# ComboBreaker.net
KiCad netlist of a schematic drawn in EAGLE
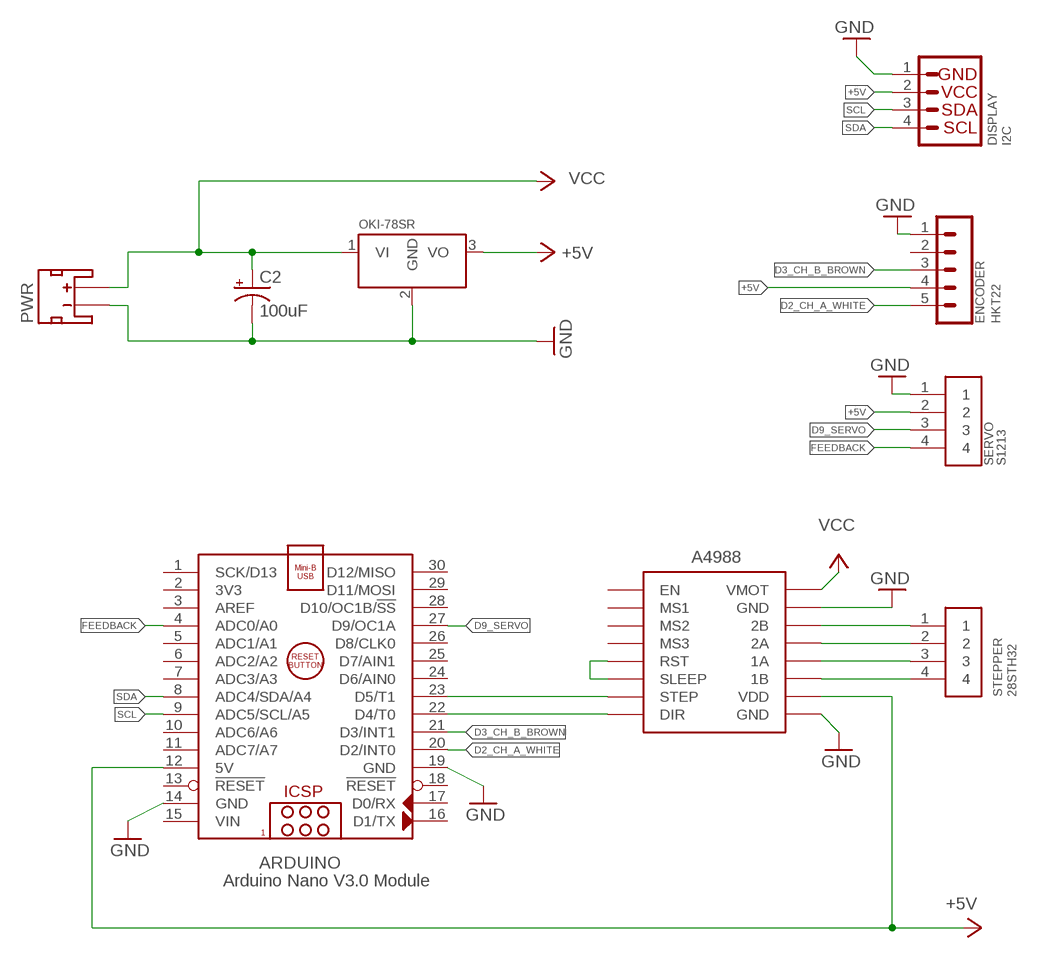
[diagram p0: schematic, sheet 1]

(export (version "E")
  (design (tool "Eeschema 10.0.6"))
  (components
    (comp (ref "A4988")
      (value "StepStick")
      (footprint "eagle-import:A4988BREAKOUT")
      (libsource (lib "eagle-import") (part "A4988BREAKOUT"))
    )
    (comp (ref "ARDUINO")
      (value "Arduino Nano V3.0 Module")
      (footprint "eagle-import:ARDUINO_NANO")
      (libsource (lib "eagle-import") (part "ARDUINO_NANO"))
    )
    (comp (ref "C2")
      (value "100uF")
      (footprint "eagle-import:E3,5-8")
      (libsource (lib "eagle-import") (part "CPOL-USE3.5-8"))
    )
    (comp (ref "DISPLAY")
      (value "I2C")
      (footprint "eagle-import:1X04")
      (libsource (lib "eagle-import") (part "I2C_STANDARD"))
    )
    (comp (ref "ENCODER")
      (value "HKT22")
      (footprint "eagle-import:CON-LSTB_MA05-1")
      (libsource (lib "eagle-import") (part "CON-LSTB_MA05-1"))
    )
    (comp (ref "OKI-78SR")
      (value "5/1.5-W36H-C")
      (footprint "eagle-import:OKI-78SRH")
      (libsource (lib "eagle-import") (part "DCDC_OKI-78SR"))
    )
    (comp (ref "PWR")
      (value "7-35v")
      (footprint "eagle-import:JST-2-SMD")
      (libsource (lib "eagle-import") (part "JST_2MM_MALE"))
    )
    (comp (ref "SERVO")
      (value "S1213")
      (footprint "eagle-import:ADAFRUIT_1X04-BIG")
      (libsource (lib "eagle-import") (part "ADAFRUIT_1X4-BIG"))
    )
    (comp (ref "STEPPER")
      (value "28STH32")
      (footprint "eagle-import:ADAFRUIT_1X04-BIG")
      (libsource (lib "eagle-import") (part "ADAFRUIT_1X4-BIG"))
    )
  )
  (nets
    (net (code "1") (name "+5V") (class "Default")
      (node (ref "A4988") (pin "VDD") (pinfunction "VDD_VDD") (pintype "power_in"))
      (node (ref "ARDUINO") (pin "12") (pinfunction "5V_12") (pintype "power_in"))
      (node (ref "DISPLAY") (pin "2") (pinfunction "2_2") (pintype "power_in"))
      (node (ref "ENCODER") (pin "4") (pinfunction "4_4") (pintype "passive"))
      (node (ref "OKI-78SR") (pin "3") (pinfunction "VO_3") (pintype "bidirectional"))
      (node (ref "SERVO") (pin "2") (pinfunction "2_2") (pintype "bidirectional"))
    )
    (net (code "2") (name "/VIN") (class "Default")
      (node (ref "ARDUINO") (pin "15") (pinfunction "VIN_15") (pintype "power_in"))
    )
    (net (code "3") (name "D2_CH_A_WHITE") (class "Default")
      (node (ref "ARDUINO") (pin "20") (pinfunction "D2/INT0_20") (pintype "bidirectional"))
      (node (ref "ENCODER") (pin "5") (pinfunction "5_5") (pintype "passive"))
    )
    (net (code "4") (name "D3_CH_B_BROWN") (class "Default")
      (node (ref "ARDUINO") (pin "21") (pinfunction "D3/INT1_21") (pintype "bidirectional"))
      (node (ref "ENCODER") (pin "3") (pinfunction "3_3") (pintype "passive"))
    )
    (net (code "5") (name "D9_SERVO") (class "Default")
      (node (ref "ARDUINO") (pin "27") (pinfunction "D9/OC1A_27") (pintype "bidirectional"))
      (node (ref "SERVO") (pin "3") (pinfunction "3_3") (pintype "bidirectional"))
    )
    (net (code "6") (name "FEEDBACK") (class "Default")
      (node (ref "ARDUINO") (pin "4") (pinfunction "ADC0/A0_4") (pintype "bidirectional"))
      (node (ref "SERVO") (pin "4") (pinfunction "4_4") (pintype "bidirectional"))
    )
    (net (code "7") (name "GND") (class "Default")
      (node (ref "A4988") (pin "GND") (pinfunction "GND_GND") (pintype "power_in"))
      (node (ref "A4988") (pin "GND@0") (pinfunction "GND_GND@0") (pintype "power_in"))
      (node (ref "ARDUINO") (pin "14") (pinfunction "GND_14") (pintype "power_in"))
      (node (ref "ARDUINO") (pin "19") (pinfunction "GND_19") (pintype "power_in"))
      (node (ref "C2") (pin "-") (pinfunction "-_-") (pintype "passive"))
      (node (ref "DISPLAY") (pin "1") (pinfunction "1_1") (pintype "power_in"))
      (node (ref "ENCODER") (pin "1") (pinfunction "1_1") (pintype "passive"))
      (node (ref "OKI-78SR") (pin "2") (pinfunction "GND_2") (pintype "bidirectional"))
      (node (ref "PWR") (pin "GND") (pinfunction "-_GND") (pintype "bidirectional"))
      (node (ref "SERVO") (pin "1") (pinfunction "1_1") (pintype "bidirectional"))
    )
    (net (code "8") (name "Net-(A4988-Pad1A)") (class "Default")
      (node (ref "A4988") (pin "1A") (pinfunction "1A_1A") (pintype "output"))
      (node (ref "STEPPER") (pin "3") (pinfunction "3_3") (pintype "bidirectional"))
    )
    (net (code "9") (name "Net-(A4988-Pad1B)") (class "Default")
      (node (ref "A4988") (pin "1B") (pinfunction "1B_1B") (pintype "output"))
      (node (ref "STEPPER") (pin "4") (pinfunction "4_4") (pintype "bidirectional"))
    )
    (net (code "10") (name "Net-(A4988-Pad2A)") (class "Default")
      (node (ref "A4988") (pin "2A") (pinfunction "2A_2A") (pintype "output"))
      (node (ref "STEPPER") (pin "2") (pinfunction "2_2") (pintype "bidirectional"))
    )
    (net (code "11") (name "Net-(A4988-Pad2B)") (class "Default")
      (node (ref "A4988") (pin "2B") (pinfunction "2B_2B") (pintype "output"))
      (node (ref "STEPPER") (pin "1") (pinfunction "1_1") (pintype "bidirectional"))
    )
    (net (code "12") (name "Net-(A4988-SLEEP)") (class "Default")
      (node (ref "A4988") (pin "RST") (pinfunction "RST_RST") (pintype "input"))
      (node (ref "A4988") (pin "SLP") (pinfunction "SLEEP_SLP") (pintype "input"))
    )
    (net (code "13") (name "Net-(ARDUINO-D4{slash}T0)") (class "Default")
      (node (ref "A4988") (pin "DIR") (pinfunction "DIR_DIR") (pintype "input"))
      (node (ref "ARDUINO") (pin "22") (pinfunction "D4/T0_22") (pintype "bidirectional"))
    )
    (net (code "14") (name "Net-(ARDUINO-D5{slash}T1)") (class "Default")
      (node (ref "A4988") (pin "STEP") (pinfunction "STEP_STEP") (pintype "input"))
      (node (ref "ARDUINO") (pin "23") (pinfunction "D5/T1_23") (pintype "bidirectional"))
    )
    (net (code "15") (name "SCL") (class "Default")
      (node (ref "ARDUINO") (pin "9") (pinfunction "ADC5/SCL/A5_9") (pintype "bidirectional"))
      (node (ref "DISPLAY") (pin "3") (pinfunction "3_3") (pintype "passive"))
    )
    (net (code "16") (name "SDA") (class "Default")
      (node (ref "ARDUINO") (pin "8") (pinfunction "ADC4/SDA/A4_8") (pintype "bidirectional"))
      (node (ref "DISPLAY") (pin "4") (pinfunction "4_4") (pintype "passive"))
    )
    (net (code "17") (name "VCC") (class "Default")
      (node (ref "A4988") (pin "VMOT") (pinfunction "VMOT_VMOT") (pintype "power_in"))
      (node (ref "C2") (pin "+") (pinfunction "+_+") (pintype "passive"))
      (node (ref "OKI-78SR") (pin "1") (pinfunction "VI_1") (pintype "bidirectional"))
      (node (ref "PWR") (pin "2") (pinfunction "+_2") (pintype "bidirectional"))
    )
    (net (code "18") (name "unconnected-(A4988-PadEN)") (class "Default")
      (node (ref "A4988") (pin "EN") (pinfunction "EN_EN") (pintype "input"))
    )
    (net (code "19") (name "unconnected-(A4988-PadMS1)") (class "Default")
      (node (ref "A4988") (pin "MS1") (pinfunction "MS1_MS1") (pintype "input"))
    )
    (net (code "20") (name "unconnected-(A4988-PadMS2)") (class "Default")
      (node (ref "A4988") (pin "MS2") (pinfunction "MS2_MS2") (pintype "input"))
    )
    (net (code "21") (name "unconnected-(A4988-PadMS3)") (class "Default")
      (node (ref "A4988") (pin "MS3") (pinfunction "MS3_MS3") (pintype "input"))
    )
    (net (code "22") (name "unconnected-(ARDUINO-3V3-Pad2)") (class "Default")
      (node (ref "ARDUINO") (pin "2") (pinfunction "3V3_2") (pintype "output"))
    )
    (net (code "23") (name "unconnected-(ARDUINO-ADC1{slash}A1-Pad5)") (class "Default")
      (node (ref "ARDUINO") (pin "5") (pinfunction "ADC1/A1_5") (pintype "bidirectional"))
    )
    (net (code "24") (name "unconnected-(ARDUINO-ADC2{slash}A2-Pad6)") (class "Default")
      (node (ref "ARDUINO") (pin "6") (pinfunction "ADC2/A2_6") (pintype "bidirectional"))
    )
    (net (code "25") (name "unconnected-(ARDUINO-ADC3{slash}A3-Pad7)") (class "Default")
      (node (ref "ARDUINO") (pin "7") (pinfunction "ADC3/A3_7") (pintype "bidirectional"))
    )
    (net (code "26") (name "unconnected-(ARDUINO-ADC6{slash}A6-Pad10)") (class "Default")
      (node (ref "ARDUINO") (pin "10") (pinfunction "ADC6/A6_10") (pintype "bidirectional"))
    )
    (net (code "27") (name "unconnected-(ARDUINO-ADC7{slash}A7-Pad11)") (class "Default")
      (node (ref "ARDUINO") (pin "11") (pinfunction "ADC7/A7_11") (pintype "bidirectional"))
    )
    (net (code "28") (name "unconnected-(ARDUINO-AREF-Pad3)") (class "Default")
      (node (ref "ARDUINO") (pin "3") (pinfunction "AREF_3") (pintype "input"))
    )
    (net (code "29") (name "unconnected-(ARDUINO-D0{slash}RX-Pad17)") (class "Default")
      (node (ref "ARDUINO") (pin "17") (pinfunction "D0/RX_17") (pintype "bidirectional"))
    )
    (net (code "30") (name "unconnected-(ARDUINO-D1{slash}TX-Pad16)") (class "Default")
      (node (ref "ARDUINO") (pin "16") (pinfunction "D1/TX_16") (pintype "bidirectional"))
    )
    (net (code "31") (name "unconnected-(ARDUINO-D6{slash}AIN0-Pad24)") (class "Default")
      (node (ref "ARDUINO") (pin "24") (pinfunction "D6/AIN0_24") (pintype "bidirectional"))
    )
    (net (code "32") (name "unconnected-(ARDUINO-D7{slash}AIN1-Pad25)") (class "Default")
      (node (ref "ARDUINO") (pin "25") (pinfunction "D7/AIN1_25") (pintype "bidirectional"))
    )
    (net (code "33") (name "unconnected-(ARDUINO-D8{slash}CLK0-Pad26)") (class "Default")
      (node (ref "ARDUINO") (pin "26") (pinfunction "D8/CLK0_26") (pintype "bidirectional"))
    )
    (net (code "34") (name "unconnected-(ARDUINO-D10{slash}OC1B{slash}~{SS}-Pad28)") (class "Default")
      (node (ref "ARDUINO") (pin "28") (pinfunction "D10/OC1B/~{SS}_28") (pintype "bidirectional"))
    )
    (net (code "35") (name "unconnected-(ARDUINO-D11{slash}MOSI-Pad29)") (class "Default")
      (node (ref "ARDUINO") (pin "29") (pinfunction "D11/MOSI_29") (pintype "bidirectional"))
    )
    (net (code "36") (name "unconnected-(ARDUINO-D12{slash}MISO-Pad30)") (class "Default")
      (node (ref "ARDUINO") (pin "30") (pinfunction "D12/MISO_30") (pintype "bidirectional"))
    )
    (net (code "37") (name "unconnected-(ARDUINO-SCK{slash}D13-Pad1)") (class "Default")
      (node (ref "ARDUINO") (pin "1") (pinfunction "SCK/D13_1") (pintype "bidirectional"))
    )
    (net (code "38") (name "unconnected-(ARDUINO-~{RESET}-Pad13)") (class "Default")
      (node (ref "ARDUINO") (pin "13") (pinfunction "~{RESET}_13") (pintype "input"))
    )
    (net (code "39") (name "unconnected-(ARDUINO-~{RESET}-Pad18)") (class "Default")
      (node (ref "ARDUINO") (pin "18") (pinfunction "~{RESET}_18") (pintype "input"))
    )
    (net (code "40") (name "unconnected-(ENCODER-Pad2)") (class "Default")
      (node (ref "ENCODER") (pin "2") (pinfunction "2_2") (pintype "passive"))
    )
    (net (code "41") (name "unconnected-(PWR-PAD1-PadNC1)") (class "Default")
      (node (ref "PWR") (pin "NC1") (pinfunction "PAD1_NC1") (pintype "bidirectional"))
    )
    (net (code "42") (name "unconnected-(PWR-PAD2-PadNC2)") (class "Default")
      (node (ref "PWR") (pin "NC2") (pinfunction "PAD2_NC2") (pintype "bidirectional"))
    )
  )
)
